# IsolatedDAC.net
KiCad netlist of a schematic drawn in Altium Designer
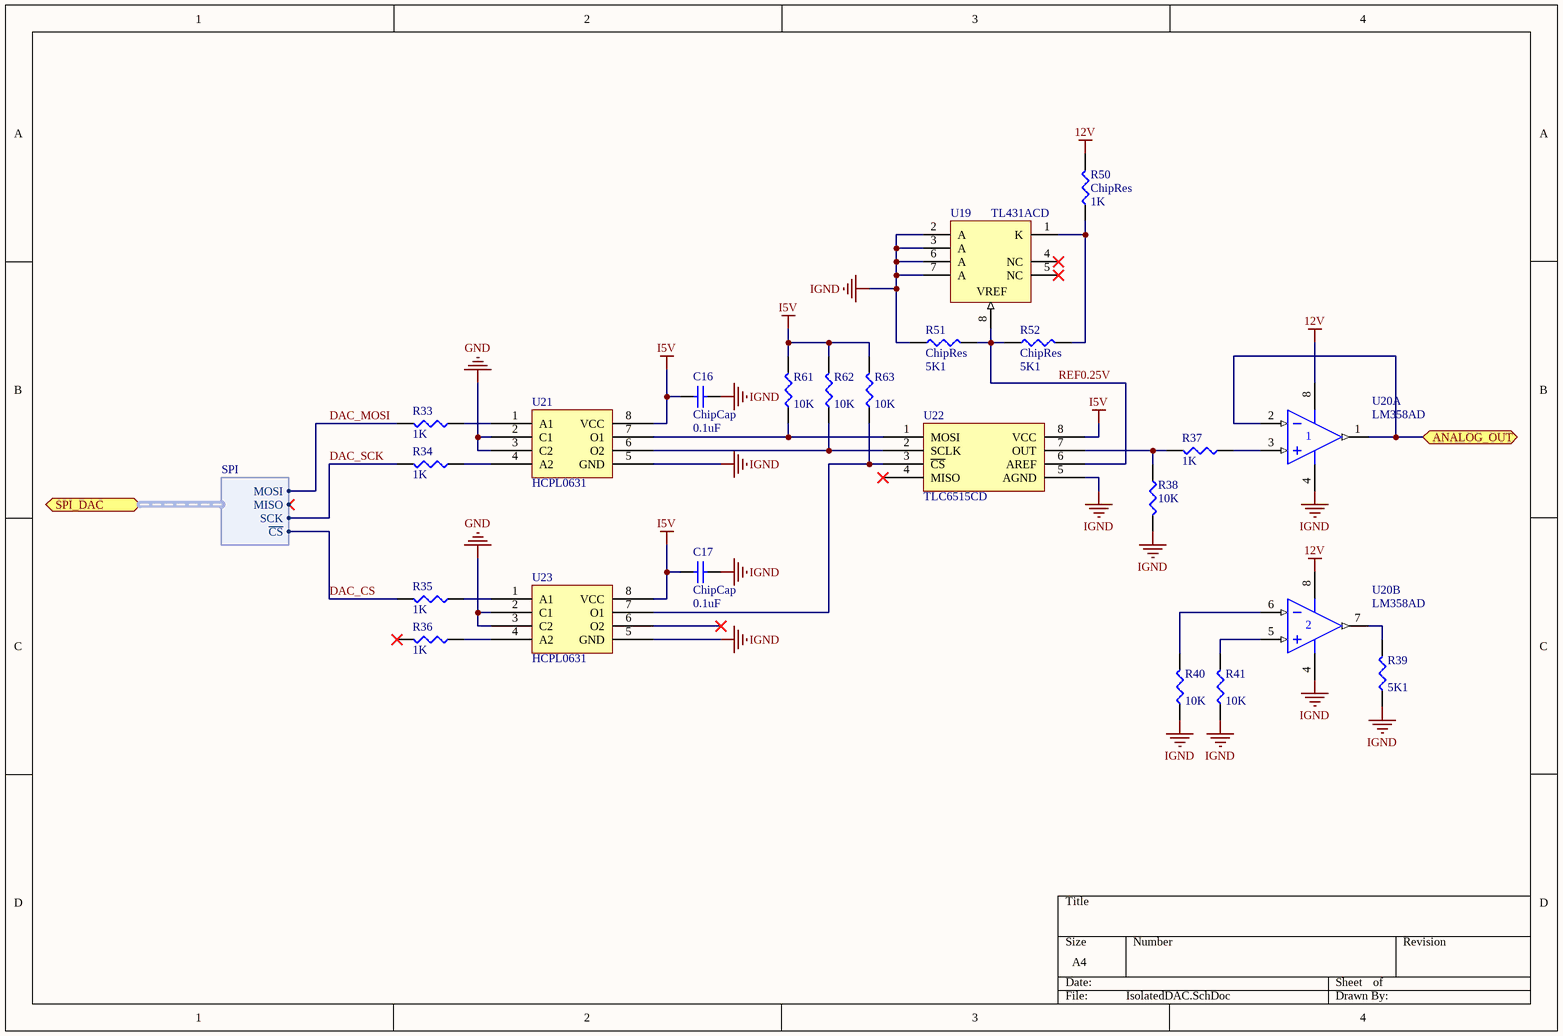
[diagram p0: IsolatedDAC.SchDoc]

(export (version "E")
  (design (tool "Eeschema 10.0.6"))
  (components
    (comp (ref "C16")
      (value "ChipCap")
      (footprint "CAP0805")
      (description "Capacitor")
      (fields (field (name "ALTIUM_VALUE") "0.1uF") (field (name "PUBLISHER") "Altium Limited"))
      (libsource (lib "Common Devices") (part "ChipCap"))
    )
    (comp (ref "C17")
      (value "ChipCap")
      (footprint "CAP0805")
      (description "Capacitor")
      (fields (field (name "ALTIUM_VALUE") "0.1uF") (field (name "PUBLISHER") "Altium Limited"))
      (libsource (lib "Common Devices") (part "ChipCap"))
    )
    (comp (ref "R33")
      (value "1K")
      (footprint "RES0805")
      (description "Chip resistor")
      (fields (field (name "Comment") "ChipRes"))
      (libsource (lib "Common Devices") (part "ChipRes"))
    )
    (comp (ref "R34")
      (value "1K")
      (footprint "RES0805")
      (description "Chip resistor")
      (fields (field (name "Comment") "ChipRes"))
      (libsource (lib "Common Devices") (part "ChipRes"))
    )
    (comp (ref "R35")
      (value "1K")
      (footprint "RES0805")
      (description "Chip resistor")
      (fields (field (name "Comment") "ChipRes"))
      (libsource (lib "Common Devices") (part "ChipRes"))
    )
    (comp (ref "R36")
      (value "1K")
      (footprint "RES0805")
      (description "Chip resistor")
      (fields (field (name "Comment") "ChipRes"))
      (libsource (lib "Common Devices") (part "ChipRes"))
    )
    (comp (ref "R37")
      (value "1K")
      (footprint "RES0805")
      (description "Chip resistor")
      (fields (field (name "Comment") "ChipRes"))
      (libsource (lib "Common Devices") (part "ChipRes"))
    )
    (comp (ref "R38")
      (value "10K")
      (footprint "RES0805")
      (description "Chip resistor")
      (fields (field (name "Comment") "ChipRes"))
      (libsource (lib "Common Devices") (part "ChipRes"))
    )
    (comp (ref "R39")
      (value "5K1")
      (footprint "RES0805")
      (description "Chip resistor")
      (fields (field (name "Comment") "ChipRes"))
      (libsource (lib "Common Devices") (part "ChipRes"))
    )
    (comp (ref "R40")
      (value "10K")
      (footprint "RES0805")
      (description "Chip resistor")
      (fields (field (name "Comment") "ChipRes"))
      (libsource (lib "Common Devices") (part "ChipRes"))
    )
    (comp (ref "R41")
      (value "10K")
      (footprint "RES0805")
      (description "Chip resistor")
      (fields (field (name "Comment") "ChipRes"))
      (libsource (lib "Common Devices") (part "ChipRes"))
    )
    (comp (ref "R50")
      (value "ChipRes")
      (footprint "RES0805")
      (description "Chip resistor")
      (fields (field (name "ALTIUM_VALUE") "1K"))
      (libsource (lib "Common Devices") (part "ChipRes"))
    )
    (comp (ref "R51")
      (value "ChipRes")
      (footprint "RES0805")
      (description "Chip resistor")
      (fields (field (name "ALTIUM_VALUE") "5K1"))
      (libsource (lib "Common Devices") (part "ChipRes"))
    )
    (comp (ref "R52")
      (value "ChipRes")
      (footprint "RES0805")
      (description "Chip resistor")
      (fields (field (name "ALTIUM_VALUE") "5K1"))
      (libsource (lib "Common Devices") (part "ChipRes"))
    )
    (comp (ref "R61")
      (value "10K")
      (footprint "RES0805")
      (description "Chip resistor")
      (fields (field (name "Comment") "ChipRes"))
      (libsource (lib "Common Devices") (part "ChipRes"))
    )
    (comp (ref "R62")
      (value "10K")
      (footprint "RES0805")
      (description "Chip resistor")
      (fields (field (name "Comment") "ChipRes"))
      (libsource (lib "Common Devices") (part "ChipRes"))
    )
    (comp (ref "R63")
      (value "10K")
      (footprint "RES0805")
      (description "Chip resistor")
      (fields (field (name "Comment") "ChipRes"))
      (libsource (lib "Common Devices") (part "ChipRes"))
    )
    (comp (ref "U19")
      (value "TL431ACD")
      (footprint "D008_N")
      (description "Adjustable Precision Shunt Regulator")
      (fields (field (name "PUBLISHER") "Altium Limited"))
      (libsource (lib "TI Power Mgt Voltage Regulator") (part "TL431ACD"))
    )
    (comp (ref "U20")
      (value "LM358AD")
      (footprint "D008_L")
      (description "Dual Operational Amplifier")
      (fields (field (name "PUBLISHER") "Altium Limited"))
      (libsource (lib "TI Operational Amplifier") (part "LM358AD"))
    )
    (comp (ref "U21")
      (value "HCPL0631")
      (footprint "SOIC8")
      (description "2-channel opto-coupler")
      (libsource (lib "Avago Optocouplers") (part "HCPL0631"))
    )
    (comp (ref "U22")
      (value "TLC6515CD")
      (footprint "SOIC8")
      (description "10-bit analog to digiyal converter")
      (fields (field (name "MANUFACTURER") "Texas Instruments"))
      (libsource (lib "TI_DigitalToAnalogConverters") (part "TLC6515"))
    )
    (comp (ref "U23")
      (value "HCPL0631")
      (footprint "SOIC8")
      (description "2-channel opto-coupler")
      (libsource (lib "Avago Optocouplers") (part "HCPL0631"))
    )
  )
  (nets
    (net (code "2") (name "/ANALOG_OUT") (class "Default")
      (node (ref "U20") (pin "1") (pinfunction "OUT_1") (pintype "output"))
      (node (ref "U20") (pin "2") (pinfunction "IN-_2") (pintype "input"))
    )
    (net (code "3") (name "/DAC_CS") (class "Default") (node (ref "R35") (pin "2") (pintype "passive")))
    (net (code "4") (name "/DAC_MOSI") (class "Default") (node (ref "R33") (pin "2") (pintype "passive")))
    (net (code "5") (name "/DAC_SCK") (class "Default") (node (ref "R34") (pin "2") (pintype "passive")))
    (net (code "6") (name "/REF0.25V") (class "Default")
      (node (ref "R51") (pin "2") (pintype "passive"))
      (node (ref "R52") (pin "1") (pintype "passive"))
      (node (ref "U19") (pin "8") (pinfunction "VREF_8") (pintype "input"))
      (node (ref "U22") (pin "6") (pinfunction "AREF_6") (pintype "passive"))
    )
    (net (code "8") (name "12V") (class "Default")
      (node (ref "R50") (pin "2") (pintype "passive"))
      (node (ref "U20") (pin "8") (pinfunction "V+_8") (pintype "power_in"))
    )
    (net (code "9") (name "GND") (class "Default")
      (node (ref "U21") (pin "2") (pinfunction "C1_2") (pintype "passive"))
      (node (ref "U21") (pin "3") (pinfunction "C2_3") (pintype "passive"))
      (node (ref "U23") (pin "2") (pinfunction "C1_2") (pintype "passive"))
      (node (ref "U23") (pin "3") (pinfunction "C2_3") (pintype "passive"))
    )
    (net (code "10") (name "I5V") (class "Default")
      (node (ref "C16") (pin "2") (pinfunction "2_2") (pintype "passive"))
      (node (ref "C17") (pin "2") (pinfunction "2_2") (pintype "passive"))
      (node (ref "R61") (pin "2") (pintype "passive"))
      (node (ref "R62") (pin "2") (pintype "passive"))
      (node (ref "R63") (pin "2") (pintype "passive"))
      (node (ref "U21") (pin "8") (pinfunction "VCC_8") (pintype "passive"))
      (node (ref "U22") (pin "8") (pinfunction "VCC_8") (pintype "passive"))
      (node (ref "U23") (pin "8") (pinfunction "VCC_8") (pintype "passive"))
    )
    (net (code "11") (name "IGND") (class "Default")
      (node (ref "C16") (pin "1") (pinfunction "1_1") (pintype "passive"))
      (node (ref "C17") (pin "1") (pinfunction "1_1") (pintype "passive"))
      (node (ref "R38") (pin "2") (pintype "passive"))
      (node (ref "R39") (pin "1") (pintype "passive"))
      (node (ref "R40") (pin "1") (pintype "passive"))
      (node (ref "R41") (pin "1") (pintype "passive"))
      (node (ref "R51") (pin "1") (pintype "passive"))
      (node (ref "U19") (pin "2") (pinfunction "A_2") (pintype "power_in"))
      (node (ref "U19") (pin "3") (pinfunction "A_3") (pintype "power_in"))
      (node (ref "U19") (pin "6") (pinfunction "A_6") (pintype "power_in"))
      (node (ref "U19") (pin "7") (pinfunction "A_7") (pintype "power_in"))
      (node (ref "U20") (pin "4") (pinfunction "V-_4") (pintype "power_in"))
      (node (ref "U21") (pin "5") (pinfunction "GND_5") (pintype "passive"))
      (node (ref "U22") (pin "5") (pinfunction "AGND_5") (pintype "passive"))
      (node (ref "U23") (pin "5") (pinfunction "GND_5") (pintype "passive"))
    )
    (net (code "12") (name "Net-(U19-K)") (class "Default")
      (node (ref "R50") (pin "1") (pintype "passive"))
      (node (ref "R52") (pin "2") (pintype "passive"))
      (node (ref "U19") (pin "1") (pinfunction "K_1") (pintype "power_in"))
    )
    (net (code "13") (name "Net-(U20A-IN+)") (class "Default")
      (node (ref "R37") (pin "1") (pintype "passive"))
      (node (ref "U20") (pin "3") (pinfunction "IN+_3") (pintype "input"))
    )
    (net (code "14") (name "Net-(U20B-IN+)") (class "Default")
      (node (ref "R41") (pin "2") (pintype "passive"))
      (node (ref "U20") (pin "5") (pinfunction "IN+_5") (pintype "input"))
    )
    (net (code "15") (name "Net-(U20B-IN-)") (class "Default")
      (node (ref "R40") (pin "2") (pintype "passive"))
      (node (ref "U20") (pin "6") (pinfunction "IN-_6") (pintype "input"))
    )
    (net (code "16") (name "Net-(U20B-OUT)") (class "Default")
      (node (ref "R39") (pin "2") (pintype "passive"))
      (node (ref "U20") (pin "7") (pinfunction "OUT_7") (pintype "output"))
    )
    (net (code "17") (name "Net-(U21-A1)") (class "Default")
      (node (ref "R33") (pin "1") (pintype "passive"))
      (node (ref "U21") (pin "1") (pinfunction "A1_1") (pintype "passive"))
    )
    (net (code "18") (name "Net-(U21-A2)") (class "Default")
      (node (ref "R34") (pin "1") (pintype "passive"))
      (node (ref "U21") (pin "4") (pinfunction "A2_4") (pintype "passive"))
    )
    (net (code "19") (name "Net-(U21-O1)") (class "Default")
      (node (ref "R61") (pin "1") (pintype "passive"))
      (node (ref "U21") (pin "7") (pinfunction "O1_7") (pintype "passive"))
      (node (ref "U22") (pin "1") (pinfunction "MOSI_1") (pintype "passive"))
    )
    (net (code "20") (name "Net-(U21-O2)") (class "Default")
      (node (ref "R62") (pin "1") (pintype "passive"))
      (node (ref "U21") (pin "6") (pinfunction "O2_6") (pintype "passive"))
      (node (ref "U22") (pin "2") (pinfunction "SCLK_2") (pintype "passive"))
    )
    (net (code "21") (name "Net-(U22-OUT)") (class "Default")
      (node (ref "R37") (pin "2") (pintype "passive"))
      (node (ref "R38") (pin "1") (pintype "passive"))
      (node (ref "U22") (pin "7") (pinfunction "OUT_7") (pintype "passive"))
    )
    (net (code "22") (name "Net-(U22-~{CS})") (class "Default")
      (node (ref "R63") (pin "1") (pintype "passive"))
      (node (ref "U22") (pin "3") (pinfunction "~{CS}_3") (pintype "passive"))
      (node (ref "U23") (pin "7") (pinfunction "O1_7") (pintype "passive"))
    )
    (net (code "23") (name "Net-(U23-A1)") (class "Default")
      (node (ref "R35") (pin "1") (pintype "passive"))
      (node (ref "U23") (pin "1") (pinfunction "A1_1") (pintype "passive"))
    )
    (net (code "24") (name "Net-(U23-A2)") (class "Default")
      (node (ref "R36") (pin "1") (pintype "passive"))
      (node (ref "U23") (pin "4") (pinfunction "A2_4") (pintype "passive"))
    )
    (net (code "25") (name "unconnected-(R36-Pad2)") (class "Default")
      (node (ref "R36") (pin "2") (pintype "passive+no_connect"))
    )
    (net (code "26") (name "unconnected-(U19-NC-Pad4)") (class "Default")
      (node (ref "U19") (pin "4") (pinfunction "NC_4") (pintype "passive+no_connect"))
    )
    (net (code "27") (name "unconnected-(U19-NC-Pad5)") (class "Default")
      (node (ref "U19") (pin "5") (pinfunction "NC_5") (pintype "passive+no_connect"))
    )
    (net (code "28") (name "unconnected-(U22-MISO-Pad4)") (class "Default")
      (node (ref "U22") (pin "4") (pinfunction "MISO_4") (pintype "passive+no_connect"))
    )
    (net (code "29") (name "unconnected-(U23-O2-Pad6)") (class "Default")
      (node (ref "U23") (pin "6") (pinfunction "O2_6") (pintype "passive+no_connect"))
    )
  )
)
